# proto.net
KiCad netlist of a schematic drawn in EAGLE
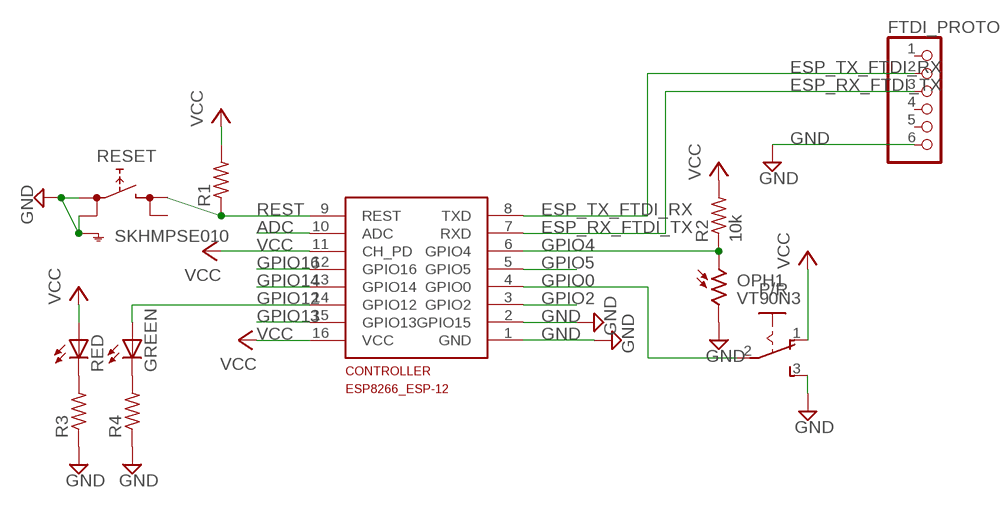
[diagram p0: schematic, sheet 1]

(export (version "E")
  (design (tool "Eeschema 10.0.6"))
  (components
    (comp (ref "CONTROLLER")
      (value "ESP8266_ESP-12")
      (footprint "eagle-import:ESP8266-ESP12")
      (libsource (lib "eagle-import") (part "ESP8266_ESP-12"))
    )
    (comp (ref "FTDI_PROTO")
      (value "PINHD-1X6")
      (footprint "eagle-import:1X06")
      (libsource (lib "eagle-import") (part "PINHD-1X6"))
    )
    (comp (ref "GREEN")
      (value "LED3MM")
      (footprint "eagle-import:LED3MM")
      (libsource (lib "eagle-import") (part "LED3MM"))
    )
    (comp (ref "OPH1")
      (value "VT90N3")
      (footprint "eagle-import:VT900")
      (libsource (lib "eagle-import") (part "VT90N3"))
    )
    (comp (ref "P/R")
      (value "255SB")
      (footprint "eagle-import:255SB")
      (libsource (lib "eagle-import") (part "255SB"))
    )
    (comp (ref "R1")
      (value "R-US_0309/12")
      (footprint "eagle-import:0309_12")
      (libsource (lib "eagle-import") (part "R-US_0309/12"))
    )
    (comp (ref "R2")
      (value "10k")
      (footprint "eagle-import:0309_12")
      (libsource (lib "eagle-import") (part "R-US_0309/12"))
    )
    (comp (ref "R3")
      (value "R-US_0309/12")
      (footprint "eagle-import:0309_12")
      (libsource (lib "eagle-import") (part "R-US_0309/12"))
    )
    (comp (ref "R4")
      (value "R-US_0309/12")
      (footprint "eagle-import:0309_12")
      (libsource (lib "eagle-import") (part "R-US_0309/12"))
    )
    (comp (ref "RED")
      (value "LED3MM")
      (footprint "eagle-import:LED3MM")
      (libsource (lib "eagle-import") (part "LED3MM"))
    )
    (comp (ref "RESET")
      (value "SKHMPSE010")
      (footprint "eagle-import:SKHMPXE010")
      (libsource (lib "eagle-import") (part "SKHMPE010S"))
    )
  )
  (nets
    (net (code "1") (name "/ADC") (class "Default")
      (node (ref "CONTROLLER") (pin "10") (pinfunction "ADC_10") (pintype "bidirectional"))
    )
    (net (code "2") (name "/ESP_RX_FTDI_TX") (class "Default")
      (node (ref "CONTROLLER") (pin "7") (pinfunction "RXD_7") (pintype "bidirectional"))
      (node (ref "FTDI_PROTO") (pin "3") (pinfunction "3_3") (pintype "passive"))
    )
    (net (code "3") (name "/ESP_TX_FTDI_RX") (class "Default")
      (node (ref "CONTROLLER") (pin "8") (pinfunction "TXD_8") (pintype "bidirectional"))
      (node (ref "FTDI_PROTO") (pin "2") (pinfunction "2_2") (pintype "passive"))
    )
    (net (code "4") (name "/GPIO0") (class "Default")
      (node (ref "CONTROLLER") (pin "4") (pinfunction "GPIO0_4") (pintype "bidirectional"))
      (node (ref "P/R") (pin "2") (pinfunction "P_2") (pintype "passive"))
    )
    (net (code "5") (name "/GPIO2") (class "Default")
      (node (ref "CONTROLLER") (pin "3") (pinfunction "GPIO2_3") (pintype "bidirectional"))
    )
    (net (code "6") (name "/GPIO4") (class "Default")
      (node (ref "CONTROLLER") (pin "6") (pinfunction "GPIO4_6") (pintype "bidirectional"))
      (node (ref "OPH1") (pin "1") (pinfunction "1_1") (pintype "passive"))
      (node (ref "R2") (pin "1") (pinfunction "1_1") (pintype "passive"))
    )
    (net (code "7") (name "/GPIO5") (class "Default")
      (node (ref "CONTROLLER") (pin "5") (pinfunction "GPIO5_5") (pintype "bidirectional"))
    )
    (net (code "8") (name "/GPIO12") (class "Default")
      (node (ref "CONTROLLER") (pin "14") (pinfunction "GPIO12_14") (pintype "bidirectional"))
      (node (ref "GREEN") (pin "A") (pinfunction "A_A") (pintype "passive"))
    )
    (net (code "9") (name "/GPIO13") (class "Default")
      (node (ref "CONTROLLER") (pin "15") (pinfunction "GPIO13_15") (pintype "bidirectional"))
    )
    (net (code "10") (name "/GPIO14") (class "Default")
      (node (ref "CONTROLLER") (pin "13") (pinfunction "GPIO14_13") (pintype "bidirectional"))
    )
    (net (code "11") (name "/GPIO16") (class "Default")
      (node (ref "CONTROLLER") (pin "12") (pinfunction "GPIO16_12") (pintype "bidirectional"))
    )
    (net (code "12") (name "/REST") (class "Default")
      (node (ref "CONTROLLER") (pin "9") (pinfunction "REST_9") (pintype "bidirectional"))
      (node (ref "R1") (pin "1") (pinfunction "1_1") (pintype "passive"))
      (node (ref "RESET") (pin "3") (pinfunction "2.1_3") (pintype "passive"))
    )
    (net (code "13") (name "GND") (class "Default")
      (node (ref "CONTROLLER") (pin "1") (pinfunction "GND_1") (pintype "bidirectional"))
      (node (ref "CONTROLLER") (pin "2") (pinfunction "GPIO15_2") (pintype "bidirectional"))
      (node (ref "FTDI_PROTO") (pin "6") (pinfunction "6_6") (pintype "passive"))
      (node (ref "OPH1") (pin "2") (pinfunction "2_2") (pintype "passive"))
      (node (ref "P/R") (pin "3") (pinfunction "S_3") (pintype "passive"))
      (node (ref "R3") (pin "1") (pinfunction "1_1") (pintype "passive"))
      (node (ref "R4") (pin "1") (pinfunction "1_1") (pintype "passive"))
      (node (ref "RESET") (pin "1") (pinfunction "1.1_1") (pintype "passive"))
      (node (ref "RESET") (pin "2") (pinfunction "1.2_2") (pintype "passive"))
      (node (ref "RESET") (pin "5") (pinfunction "SH_5") (pintype "passive"))
    )
    (net (code "14") (name "Net-(GREEN-C)") (class "Default")
      (node (ref "GREEN") (pin "K") (pinfunction "C_K") (pintype "passive"))
      (node (ref "R4") (pin "2") (pinfunction "2_2") (pintype "passive"))
    )
    (net (code "15") (name "Net-(RED-C)") (class "Default")
      (node (ref "R3") (pin "2") (pinfunction "2_2") (pintype "passive"))
      (node (ref "RED") (pin "K") (pinfunction "C_K") (pintype "passive"))
    )
    (net (code "16") (name "VCC") (class "Default")
      (node (ref "CONTROLLER") (pin "11") (pinfunction "CH_PD_11") (pintype "bidirectional"))
      (node (ref "CONTROLLER") (pin "16") (pinfunction "VCC_16") (pintype "bidirectional"))
      (node (ref "P/R") (pin "1") (pinfunction "O_1") (pintype "passive"))
      (node (ref "R1") (pin "2") (pinfunction "2_2") (pintype "passive"))
      (node (ref "R2") (pin "2") (pinfunction "2_2") (pintype "passive"))
      (node (ref "RED") (pin "A") (pinfunction "A_A") (pintype "passive"))
    )
    (net (code "17") (name "unconnected-(FTDI_PROTO-Pad1)") (class "Default")
      (node (ref "FTDI_PROTO") (pin "1") (pinfunction "1_1") (pintype "passive"))
    )
    (net (code "18") (name "unconnected-(FTDI_PROTO-Pad4)") (class "Default")
      (node (ref "FTDI_PROTO") (pin "4") (pinfunction "4_4") (pintype "passive"))
    )
    (net (code "19") (name "unconnected-(FTDI_PROTO-Pad5)") (class "Default")
      (node (ref "FTDI_PROTO") (pin "5") (pinfunction "5_5") (pintype "passive"))
    )
    (net (code "20") (name "unconnected-(RESET-2.2-Pad4)") (class "Default")
      (node (ref "RESET") (pin "4") (pinfunction "2.2_4") (pintype "passive"))
    )
  )
)
